# I2C.net
KiCad netlist of a schematic drawn in Altium Designer
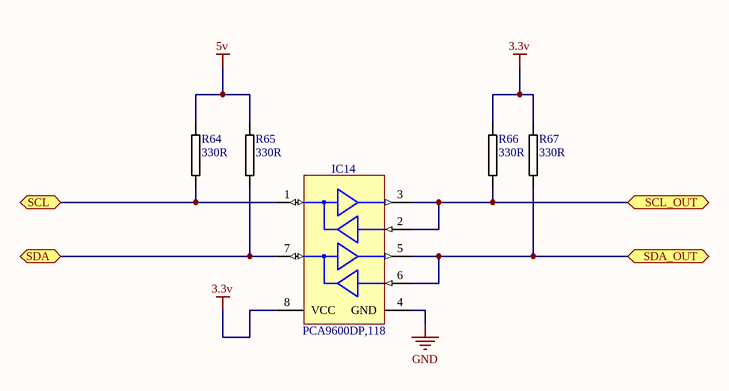
[diagram p0: I2C.SchDoc]

(export (version "E")
  (design (tool "Eeschema 10.0.6"))
  (components
    (comp (ref "IC14")
      (value "PCA9600DP,118")
      (footprint "SOP65P490X110-8N")
      (description "Dual Bidirectional Bus Buffer")
      (fields (field (name "MANUFACTURER") "NXP SEMICONDUCTORS") (field (name "AUTHOR") "CERN DEM JLC"))
      (libsource (lib "ICs And Semiconductors") (part "PCA9600"))
    )
    (comp (ref "R64")
      (value "330R")
      (footprint "0805R-330")
      (description "RESISTOR 0805 1/4 WATT THIN FILM")
      (libsource (lib "vh_altium_library") (part "0805R-330"))
    )
    (comp (ref "R65")
      (value "330R")
      (footprint "0805R-330")
      (description "RESISTOR 0805 1/4 WATT THIN FILM")
      (libsource (lib "vh_altium_library") (part "0805R-330"))
    )
    (comp (ref "R66")
      (value "330R")
      (footprint "0805R-330")
      (description "RESISTOR 0805 1/4 WATT THIN FILM")
      (libsource (lib "vh_altium_library") (part "0805R-330"))
    )
    (comp (ref "R67")
      (value "330R")
      (footprint "0805R-330")
      (description "RESISTOR 0805 1/4 WATT THIN FILM")
      (libsource (lib "vh_altium_library") (part "0805R-330"))
    )
  )
  (nets
    (net (code "1") (name "/SCL") (class "Default")
      (node (ref "IC14") (pin "1") (pinfunction "Sx_1") (pintype "bidirectional"))
      (node (ref "R64") (pin "2") (pintype "passive"))
    )
    (net (code "2") (name "/SCL_OUT") (class "Default")
      (node (ref "IC14") (pin "2") (pinfunction "Rx_2") (pintype "input"))
      (node (ref "IC14") (pin "3") (pinfunction "Tx_3") (pintype "output"))
      (node (ref "R66") (pin "2") (pintype "passive"))
    )
    (net (code "3") (name "/SDA") (class "Default")
      (node (ref "IC14") (pin "7") (pinfunction "Sy_7") (pintype "bidirectional"))
      (node (ref "R65") (pin "2") (pintype "passive"))
    )
    (net (code "4") (name "/SDA_OUT") (class "Default")
      (node (ref "IC14") (pin "5") (pinfunction "Ty_5") (pintype "output"))
      (node (ref "IC14") (pin "6") (pinfunction "Ry_6") (pintype "input"))
      (node (ref "R67") (pin "2") (pintype "passive"))
    )
    (net (code "5") (name "3.3v") (class "Default")
      (node (ref "IC14") (pin "8") (pinfunction "VCC_8") (pintype "power_in"))
      (node (ref "R66") (pin "1") (pintype "passive"))
      (node (ref "R67") (pin "1") (pintype "passive"))
    )
    (net (code "6") (name "5v") (class "Default")
      (node (ref "R64") (pin "1") (pintype "passive"))
      (node (ref "R65") (pin "1") (pintype "passive"))
    )
    (net (code "7") (name "GND") (class "Default")
      (node (ref "IC14") (pin "4") (pinfunction "GND_4") (pintype "power_in"))
    )
  )
)
